# SCH_Stepper-Spindle-Controller_2024-04-3.net
KiCad netlist of a schematic drawn in EasyEDA
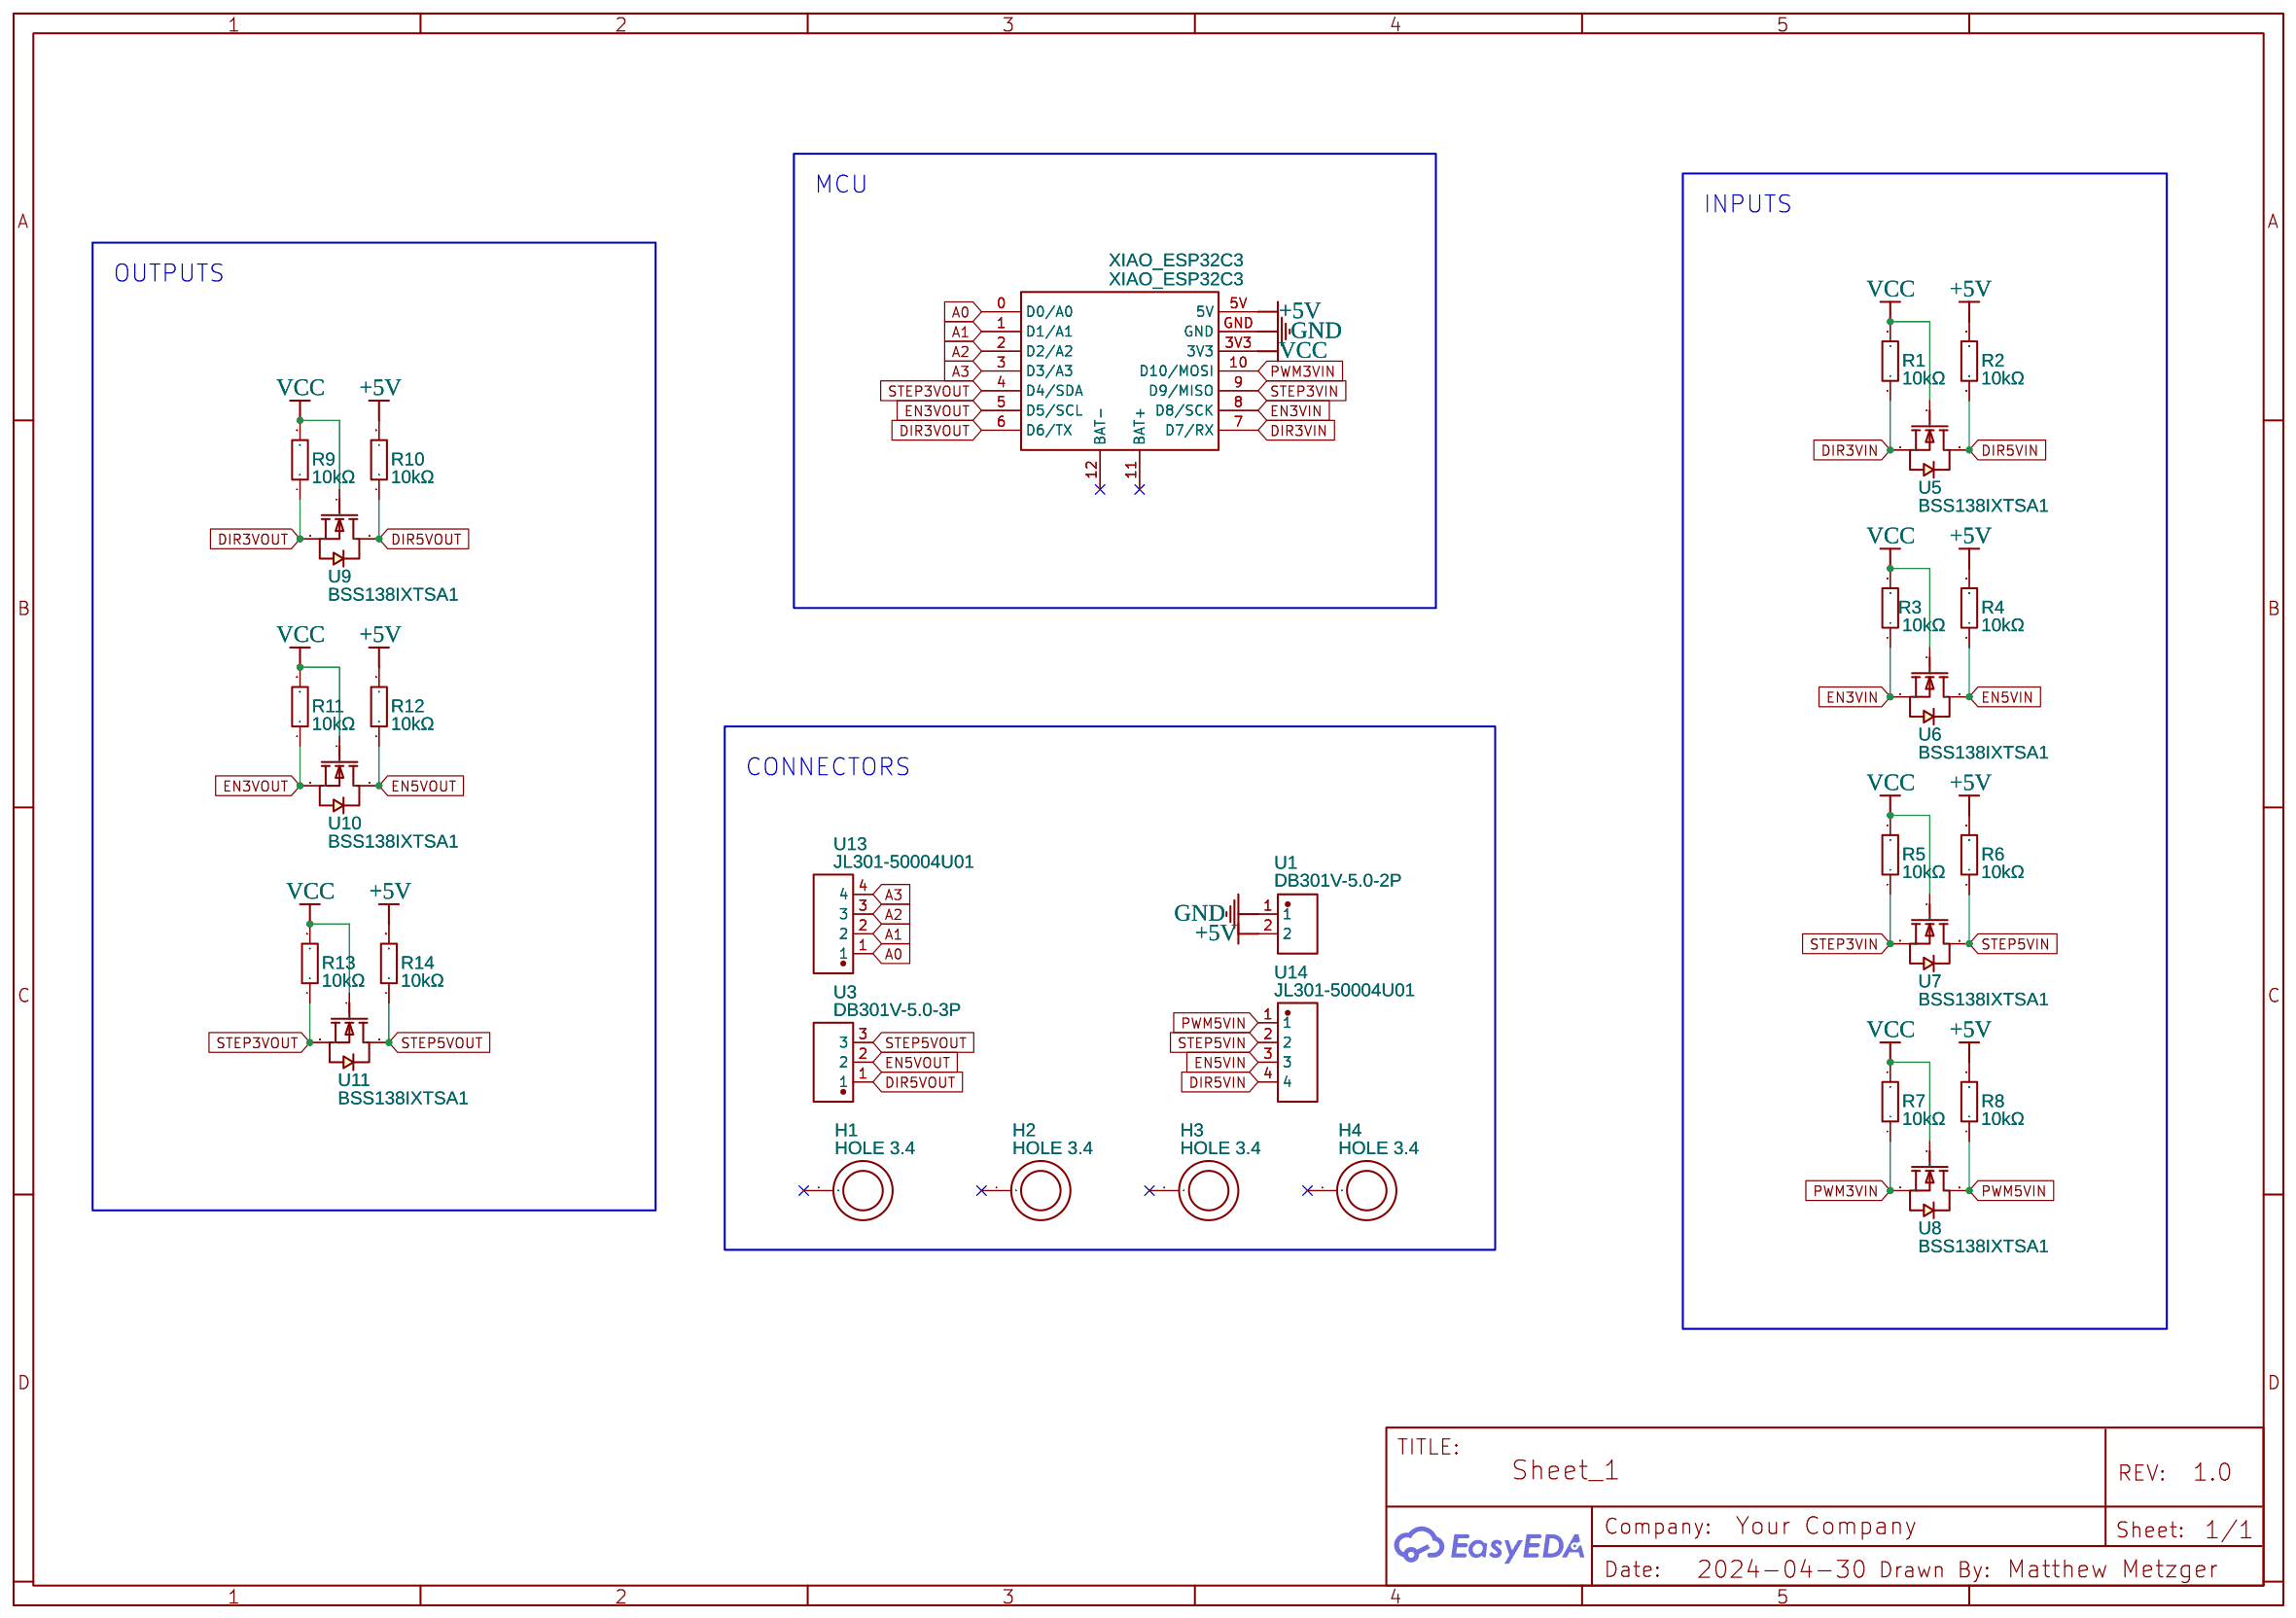
[diagram p0: schematic sheet]

(export (version "E")
  (design (tool "Eeschema 10.0.6"))
  (components
    (comp (ref "H1") (value "HOLE 3.4") (libsource (lib "") (part "HOLE 3.4")))
    (comp (ref "H2") (value "HOLE 3.4") (libsource (lib "") (part "HOLE 3.4")))
    (comp (ref "H3") (value "HOLE 3.4") (libsource (lib "") (part "HOLE 3.4")))
    (comp (ref "H4") (value "HOLE 3.4") (libsource (lib "") (part "HOLE 3.4")))
    (comp (ref "R1")
      (value "10kΩ")
      (fields (field (name "Manufacturer Part") "ERA2AEB103X") (field (name "Manufacturer") "PANASONIC(松下)"))
      (libsource (lib "") (part "ERA2AEB103X"))
    )
    (comp (ref "R2")
      (value "10kΩ")
      (fields (field (name "Manufacturer Part") "ERA2AEB103X") (field (name "Manufacturer") "PANASONIC(松下)"))
      (libsource (lib "") (part "ERA2AEB103X"))
    )
    (comp (ref "R3")
      (value "10kΩ")
      (fields (field (name "Manufacturer Part") "ERA2AEB103X") (field (name "Manufacturer") "PANASONIC(松下)"))
      (libsource (lib "") (part "ERA2AEB103X"))
    )
    (comp (ref "R4")
      (value "10kΩ")
      (fields (field (name "Manufacturer Part") "ERA2AEB103X") (field (name "Manufacturer") "PANASONIC(松下)"))
      (libsource (lib "") (part "ERA2AEB103X"))
    )
    (comp (ref "R5")
      (value "10kΩ")
      (fields (field (name "Manufacturer Part") "ERA2AEB103X") (field (name "Manufacturer") "PANASONIC(松下)"))
      (libsource (lib "") (part "ERA2AEB103X"))
    )
    (comp (ref "R6")
      (value "10kΩ")
      (fields (field (name "Manufacturer Part") "ERA2AEB103X") (field (name "Manufacturer") "PANASONIC(松下)"))
      (libsource (lib "") (part "ERA2AEB103X"))
    )
    (comp (ref "R7")
      (value "10kΩ")
      (fields (field (name "Manufacturer Part") "ERA2AEB103X") (field (name "Manufacturer") "PANASONIC(松下)"))
      (libsource (lib "") (part "ERA2AEB103X"))
    )
    (comp (ref "R8")
      (value "10kΩ")
      (fields (field (name "Manufacturer Part") "ERA2AEB103X") (field (name "Manufacturer") "PANASONIC(松下)"))
      (libsource (lib "") (part "ERA2AEB103X"))
    )
    (comp (ref "R9")
      (value "10kΩ")
      (fields (field (name "Manufacturer Part") "ERA2AEB103X") (field (name "Manufacturer") "PANASONIC(松下)"))
      (libsource (lib "") (part "ERA2AEB103X"))
    )
    (comp (ref "R10")
      (value "10kΩ")
      (fields (field (name "Manufacturer Part") "ERA2AEB103X") (field (name "Manufacturer") "PANASONIC(松下)"))
      (libsource (lib "") (part "ERA2AEB103X"))
    )
    (comp (ref "R11")
      (value "10kΩ")
      (fields (field (name "Manufacturer Part") "ERA2AEB103X") (field (name "Manufacturer") "PANASONIC(松下)"))
      (libsource (lib "") (part "ERA2AEB103X"))
    )
    (comp (ref "R12")
      (value "10kΩ")
      (fields (field (name "Manufacturer Part") "ERA2AEB103X") (field (name "Manufacturer") "PANASONIC(松下)"))
      (libsource (lib "") (part "ERA2AEB103X"))
    )
    (comp (ref "R13")
      (value "10kΩ")
      (fields (field (name "Manufacturer Part") "ERA2AEB103X") (field (name "Manufacturer") "PANASONIC(松下)"))
      (libsource (lib "") (part "ERA2AEB103X"))
    )
    (comp (ref "R14")
      (value "10kΩ")
      (fields (field (name "Manufacturer Part") "ERA2AEB103X") (field (name "Manufacturer") "PANASONIC(松下)"))
      (libsource (lib "") (part "ERA2AEB103X"))
    )
    (comp (ref "U1")
      (value "DB301V-5.0-2P")
      (fields
        (field (name "Manufacturer Part") "DB301V-5.0-2P-BU-S")
        (field (name "Manufacturer") "DORABO(地博电气)")
      )
      (libsource (lib "") (part "DB301V-5.0-2P"))
    )
    (comp (ref "U3")
      (value "DB301V-5.0-3P")
      (fields
        (field (name "Manufacturer Part") "DB301V-5.0-3P-BU-S")
        (field (name "Manufacturer") "DORABO(地博电气)")
      )
      (libsource (lib "") (part "DB301V-5.0-3P"))
    )
    (comp (ref "U5")
      (value "BSS138IXTSA1")
      (fields (field (name "Manufacturer") "Infineon(英飞凌)"))
      (libsource (lib "") (part "BSS138IXTSA1"))
    )
    (comp (ref "U6")
      (value "BSS138IXTSA1")
      (fields (field (name "Manufacturer") "Infineon(英飞凌)"))
      (libsource (lib "") (part "BSS138IXTSA1"))
    )
    (comp (ref "U7")
      (value "BSS138IXTSA1")
      (fields (field (name "Manufacturer") "Infineon(英飞凌)"))
      (libsource (lib "") (part "BSS138IXTSA1"))
    )
    (comp (ref "U8")
      (value "BSS138IXTSA1")
      (fields (field (name "Manufacturer") "Infineon(英飞凌)"))
      (libsource (lib "") (part "BSS138IXTSA1"))
    )
    (comp (ref "U9")
      (value "BSS138IXTSA1")
      (fields (field (name "Manufacturer") "Infineon(英飞凌)"))
      (libsource (lib "") (part "BSS138IXTSA1"))
    )
    (comp (ref "U10")
      (value "BSS138IXTSA1")
      (fields (field (name "Manufacturer") "Infineon(英飞凌)"))
      (libsource (lib "") (part "BSS138IXTSA1"))
    )
    (comp (ref "U11")
      (value "BSS138IXTSA1")
      (fields (field (name "Manufacturer") "Infineon(英飞凌)"))
      (libsource (lib "") (part "BSS138IXTSA1"))
    )
    (comp (ref "U13")
      (value "JL301-50004U01")
      (fields (field (name "Manufacturer") "JILN(锦凌)"))
      (libsource (lib "") (part "JL301-50004U01"))
    )
    (comp (ref "U14")
      (value "JL301-50004U01")
      (fields (field (name "Manufacturer") "JILN(锦凌)"))
      (libsource (lib "") (part "JL301-50004U01_1"))
    )
    (comp (ref "XIAO_ESP32C3")
      (value "XIAO_ESP32C3")
      (fields (field (name "Manufacturer Part") "XIAO ESP32C3") (field (name "Manufacturer") "SeeedStudio"))
      (libsource (lib "") (part "XIAO_ESP32C3"))
    )
  )
  (nets
    (net (code "1") (name "+5V") (class "Default")
      (node (ref "R10") (pin "2") (pinfunction "2_2") (pintype "input"))
      (node (ref "R12") (pin "2") (pinfunction "2_2") (pintype "input"))
      (node (ref "R14") (pin "2") (pinfunction "2_2") (pintype "input"))
      (node (ref "R2") (pin "2") (pinfunction "2_2") (pintype "input"))
      (node (ref "R4") (pin "2") (pinfunction "2_2") (pintype "input"))
      (node (ref "R6") (pin "2") (pinfunction "2_2") (pintype "input"))
      (node (ref "R8") (pin "2") (pinfunction "2_2") (pintype "input"))
      (node (ref "U1") (pin "2") (pinfunction "2_2") (pintype "unspecified"))
      (node (ref "XIAO_ESP32C3") (pin "5V") (pinfunction "5V_5V") (pintype "unspecified"))
    )
    (net (code "2") (name "A0") (class "Default")
      (node (ref "U13") (pin "1") (pinfunction "1_1") (pintype "unspecified"))
      (node (ref "XIAO_ESP32C3") (pin "0") (pinfunction "D0/A0_0") (pintype "unspecified"))
    )
    (net (code "3") (name "A1") (class "Default")
      (node (ref "U13") (pin "2") (pinfunction "2_2") (pintype "unspecified"))
      (node (ref "XIAO_ESP32C3") (pin "1") (pinfunction "D1/A1_1") (pintype "unspecified"))
    )
    (net (code "4") (name "A2") (class "Default")
      (node (ref "U13") (pin "3") (pinfunction "3_3") (pintype "unspecified"))
      (node (ref "XIAO_ESP32C3") (pin "2") (pinfunction "D2/A2_2") (pintype "unspecified"))
    )
    (net (code "5") (name "A3") (class "Default")
      (node (ref "U13") (pin "4") (pinfunction "4_4") (pintype "unspecified"))
      (node (ref "XIAO_ESP32C3") (pin "3") (pinfunction "D3/A3_3") (pintype "unspecified"))
    )
    (net (code "6") (name "DIR3VIN") (class "Default")
      (node (ref "R1") (pin "1") (pinfunction "1_1") (pintype "input"))
      (node (ref "U5") (pin "2") (pinfunction "S_2") (pintype "unspecified"))
      (node (ref "XIAO_ESP32C3") (pin "7") (pinfunction "D7/RX_7") (pintype "unspecified"))
    )
    (net (code "7") (name "DIR3VOUT") (class "Default")
      (node (ref "R9") (pin "1") (pinfunction "1_1") (pintype "input"))
      (node (ref "U9") (pin "2") (pinfunction "S_2") (pintype "unspecified"))
      (node (ref "XIAO_ESP32C3") (pin "6") (pinfunction "D6/TX_6") (pintype "unspecified"))
    )
    (net (code "8") (name "DIR5VIN") (class "Default")
      (node (ref "R2") (pin "1") (pinfunction "1_1") (pintype "input"))
      (node (ref "U14") (pin "4") (pinfunction "4_4") (pintype "unspecified"))
      (node (ref "U5") (pin "3") (pinfunction "D_3") (pintype "unspecified"))
    )
    (net (code "9") (name "DIR5VOUT") (class "Default")
      (node (ref "R10") (pin "1") (pinfunction "1_1") (pintype "input"))
      (node (ref "U3") (pin "1") (pinfunction "1_1") (pintype "unspecified"))
      (node (ref "U9") (pin "3") (pinfunction "D_3") (pintype "unspecified"))
    )
    (net (code "10") (name "EN3VIN") (class "Default")
      (node (ref "R3") (pin "1") (pinfunction "1_1") (pintype "input"))
      (node (ref "U6") (pin "2") (pinfunction "S_2") (pintype "unspecified"))
      (node (ref "XIAO_ESP32C3") (pin "8") (pinfunction "D8/SCK_8") (pintype "unspecified"))
    )
    (net (code "11") (name "EN3VOUT") (class "Default")
      (node (ref "R11") (pin "1") (pinfunction "1_1") (pintype "input"))
      (node (ref "U10") (pin "2") (pinfunction "S_2") (pintype "unspecified"))
      (node (ref "XIAO_ESP32C3") (pin "5") (pinfunction "D5/SCL_5") (pintype "unspecified"))
    )
    (net (code "12") (name "EN5VIN") (class "Default")
      (node (ref "R4") (pin "1") (pinfunction "1_1") (pintype "input"))
      (node (ref "U14") (pin "3") (pinfunction "3_3") (pintype "unspecified"))
      (node (ref "U6") (pin "3") (pinfunction "D_3") (pintype "unspecified"))
    )
    (net (code "13") (name "EN5VOUT") (class "Default")
      (node (ref "R12") (pin "1") (pinfunction "1_1") (pintype "input"))
      (node (ref "U10") (pin "3") (pinfunction "D_3") (pintype "unspecified"))
      (node (ref "U3") (pin "2") (pinfunction "2_2") (pintype "unspecified"))
    )
    (net (code "14") (name "GND") (class "Default")
      (node (ref "U1") (pin "1") (pinfunction "1_1") (pintype "unspecified"))
      (node (ref "XIAO_ESP32C3") (pin "GND") (pinfunction "GND_GND") (pintype "unspecified"))
    )
    (net (code "15") (name "PWM3VIN") (class "Default")
      (node (ref "R7") (pin "1") (pinfunction "1_1") (pintype "input"))
      (node (ref "U8") (pin "2") (pinfunction "S_2") (pintype "unspecified"))
      (node (ref "XIAO_ESP32C3") (pin "10") (pinfunction "D10/MOSI_10") (pintype "unspecified"))
    )
    (net (code "16") (name "PWM5VIN") (class "Default")
      (node (ref "R8") (pin "1") (pinfunction "1_1") (pintype "input"))
      (node (ref "U14") (pin "1") (pinfunction "1_1") (pintype "unspecified"))
      (node (ref "U8") (pin "3") (pinfunction "D_3") (pintype "unspecified"))
    )
    (net (code "17") (name "STEP3VIN") (class "Default")
      (node (ref "R5") (pin "1") (pinfunction "1_1") (pintype "input"))
      (node (ref "U7") (pin "2") (pinfunction "S_2") (pintype "unspecified"))
      (node (ref "XIAO_ESP32C3") (pin "9") (pinfunction "D9/MISO_9") (pintype "unspecified"))
    )
    (net (code "18") (name "STEP3VOUT") (class "Default")
      (node (ref "R13") (pin "1") (pinfunction "1_1") (pintype "input"))
      (node (ref "U11") (pin "2") (pinfunction "S_2") (pintype "unspecified"))
      (node (ref "XIAO_ESP32C3") (pin "4") (pinfunction "D4/SDA_4") (pintype "unspecified"))
    )
    (net (code "19") (name "STEP5VIN") (class "Default")
      (node (ref "R6") (pin "1") (pinfunction "1_1") (pintype "input"))
      (node (ref "U14") (pin "2") (pinfunction "2_2") (pintype "unspecified"))
      (node (ref "U7") (pin "3") (pinfunction "D_3") (pintype "unspecified"))
    )
    (net (code "20") (name "STEP5VOUT") (class "Default")
      (node (ref "R14") (pin "1") (pinfunction "1_1") (pintype "input"))
      (node (ref "U11") (pin "3") (pinfunction "D_3") (pintype "unspecified"))
      (node (ref "U3") (pin "3") (pinfunction "3_3") (pintype "unspecified"))
    )
    (net (code "21") (name "VCC") (class "Default")
      (node (ref "R1") (pin "2") (pinfunction "2_2") (pintype "input"))
      (node (ref "R11") (pin "2") (pinfunction "2_2") (pintype "input"))
      (node (ref "R13") (pin "2") (pinfunction "2_2") (pintype "input"))
      (node (ref "R3") (pin "2") (pinfunction "2_2") (pintype "input"))
      (node (ref "R5") (pin "2") (pinfunction "2_2") (pintype "input"))
      (node (ref "R7") (pin "2") (pinfunction "2_2") (pintype "input"))
      (node (ref "R9") (pin "2") (pinfunction "2_2") (pintype "input"))
      (node (ref "U10") (pin "1") (pinfunction "G_1") (pintype "unspecified"))
      (node (ref "U11") (pin "1") (pinfunction "G_1") (pintype "unspecified"))
      (node (ref "U5") (pin "1") (pinfunction "G_1") (pintype "unspecified"))
      (node (ref "U6") (pin "1") (pinfunction "G_1") (pintype "unspecified"))
      (node (ref "U7") (pin "1") (pinfunction "G_1") (pintype "unspecified"))
      (node (ref "U8") (pin "1") (pinfunction "G_1") (pintype "unspecified"))
      (node (ref "U9") (pin "1") (pinfunction "G_1") (pintype "unspecified"))
      (node (ref "XIAO_ESP32C3") (pin "3V3") (pinfunction "3V3_3V3") (pintype "unspecified"))
    )
    (net (code "22") (name "unconnected-(H1-Pad1)") (class "Default")
      (node (ref "H1") (pin "1") (pinfunction "1_1") (pintype "bidirectional+no_connect"))
    )
    (net (code "23") (name "unconnected-(H2-Pad1)") (class "Default")
      (node (ref "H2") (pin "1") (pinfunction "1_1") (pintype "bidirectional+no_connect"))
    )
    (net (code "24") (name "unconnected-(H3-Pad1)") (class "Default")
      (node (ref "H3") (pin "1") (pinfunction "1_1") (pintype "bidirectional+no_connect"))
    )
    (net (code "25") (name "unconnected-(H4-Pad1)") (class "Default")
      (node (ref "H4") (pin "1") (pinfunction "1_1") (pintype "bidirectional+no_connect"))
    )
    (net (code "26") (name "unconnected-(XIAO_ESP32C3-BAT+-Pad11)") (class "Default")
      (node (ref "XIAO_ESP32C3") (pin "11") (pinfunction "BAT+_11") (pintype "unspecified+no_connect"))
    )
    (net (code "27") (name "unconnected-(XIAO_ESP32C3-BAT--Pad12)") (class "Default")
      (node (ref "XIAO_ESP32C3") (pin "12") (pinfunction "BAT-_12") (pintype "unspecified+no_connect"))
    )
  )
)
